# 20_character_HP_DL1414_display_with_SN74.net
KiCad netlist of a schematic drawn in EasyEDA
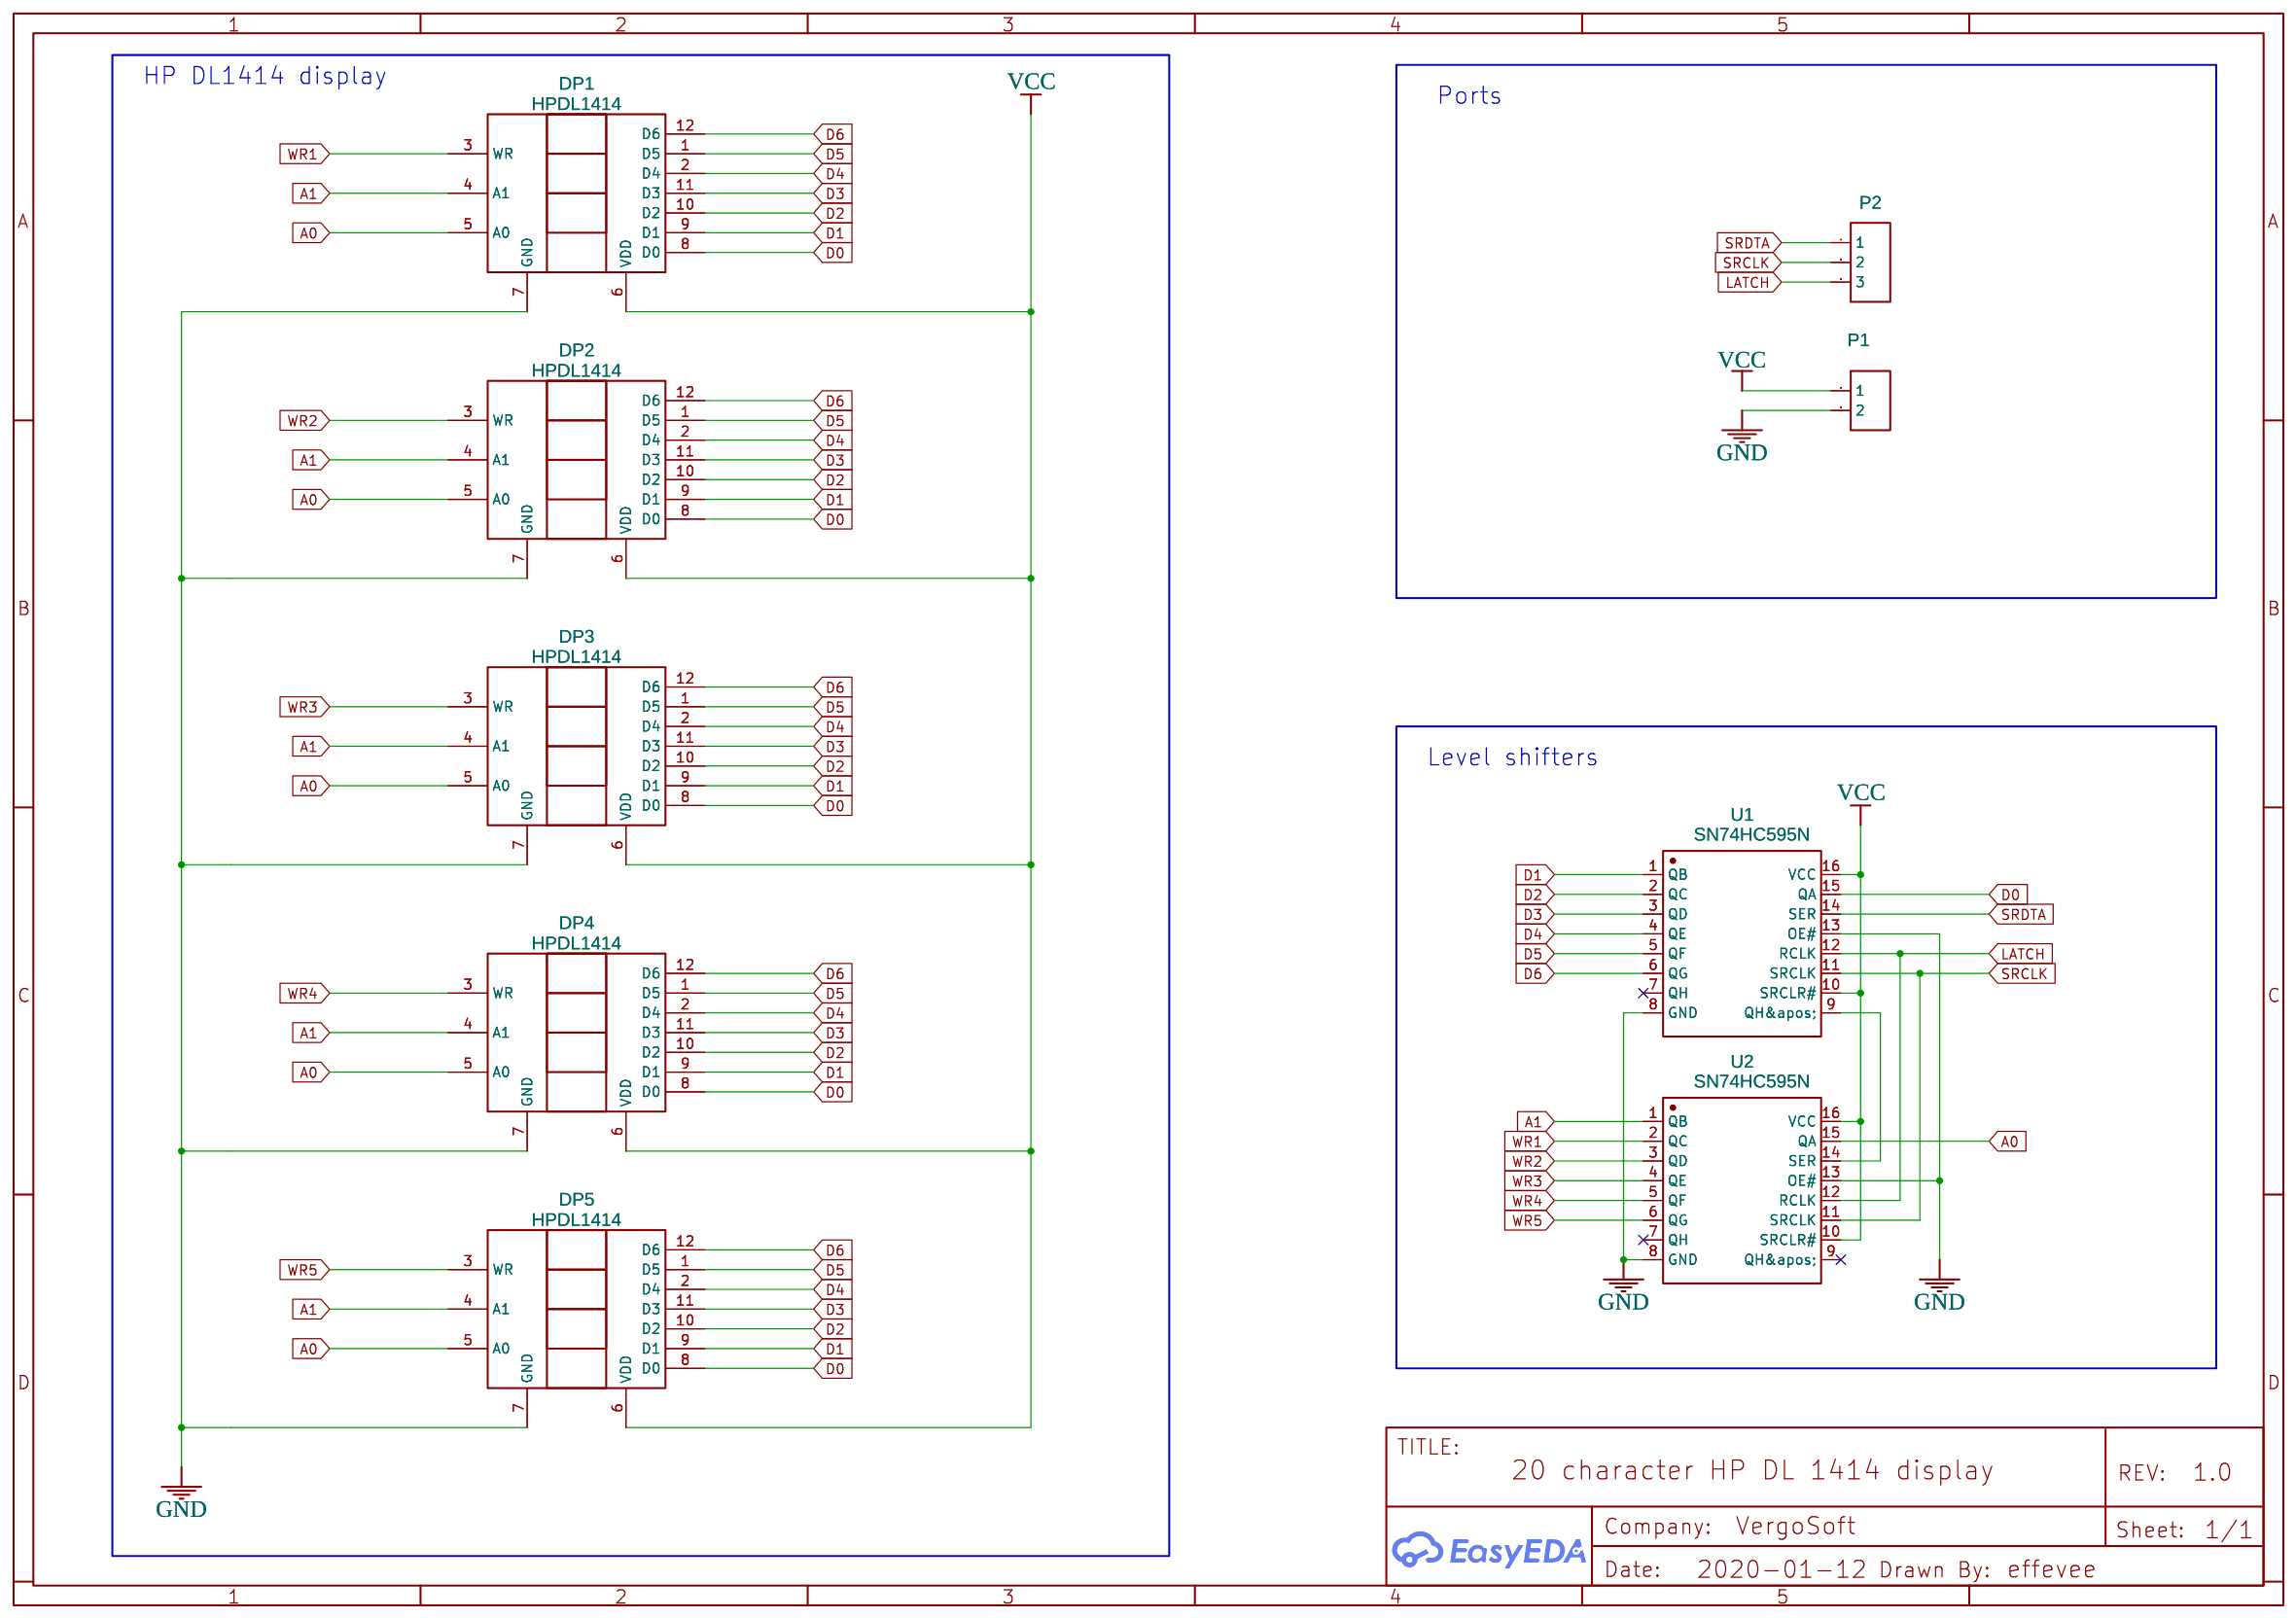
[diagram p0: schematic sheet]

(export (version "E")
  (design (tool "Eeschema 10.0.6"))
  (components
    (comp (ref "DP1")
      (value "HPDL1414")
      (fields (field (name "BOM_Supplier Part") "HPDL-1414"))
      (libsource (lib "") (part "HPDL1414 EFFEVEE"))
    )
    (comp (ref "DP2")
      (value "HPDL1414")
      (fields (field (name "BOM_Supplier Part") "HPDL-1414"))
      (libsource (lib "") (part "HPDL1414 EFFEVEE"))
    )
    (comp (ref "DP3")
      (value "HPDL1414")
      (fields (field (name "BOM_Supplier Part") "HPDL-1414"))
      (libsource (lib "") (part "HPDL1414 EFFEVEE"))
    )
    (comp (ref "DP4")
      (value "HPDL1414")
      (fields (field (name "BOM_Supplier Part") "HPDL-1414"))
      (libsource (lib "") (part "HPDL1414 EFFEVEE"))
    )
    (comp (ref "DP5")
      (value "HPDL1414")
      (fields (field (name "BOM_Supplier Part") "HPDL-1414"))
      (libsource (lib "") (part "HPDL1414 EFFEVEE"))
    )
    (comp (ref "P1")
      (value "Header-Female-2.54_1x2")
      (fields
        (field (name "BOM_Manufacturer Part") "2.54-1*2PFemale")
        (field (name "BOM_Supplier Part") "C49661")
      )
      (libsource (lib "") (part "Header-Female-2.54_1x2"))
    )
    (comp (ref "P2")
      (value "Header-Female-2.54_1x3")
      (fields (field (name "BOM_Supplier Part") "C146243"))
      (libsource (lib "") (part "Header-Female-2.54_1x3"))
    )
    (comp (ref "U1")
      (value "SN74HC595N")
      (fields (field (name "BOM_Supplier Part") "C78711"))
      (libsource (lib "") (part "SN74HC595N"))
    )
    (comp (ref "U2")
      (value "SN74HC595N")
      (fields (field (name "BOM_Supplier Part") "C78711"))
      (libsource (lib "") (part "SN74HC595N"))
    )
  )
  (nets
    (net (code "1") (name "A0") (class "Default")
      (node (ref "DP1") (pin "5") (pinfunction "A0_5") (pintype "unspecified"))
      (node (ref "DP2") (pin "5") (pinfunction "A0_5") (pintype "unspecified"))
      (node (ref "DP3") (pin "5") (pinfunction "A0_5") (pintype "unspecified"))
      (node (ref "DP4") (pin "5") (pinfunction "A0_5") (pintype "unspecified"))
      (node (ref "DP5") (pin "5") (pinfunction "A0_5") (pintype "unspecified"))
      (node (ref "U2") (pin "15") (pinfunction "QA_15") (pintype "unspecified"))
    )
    (net (code "2") (name "A1") (class "Default")
      (node (ref "DP1") (pin "4") (pinfunction "A1_4") (pintype "unspecified"))
      (node (ref "DP2") (pin "4") (pinfunction "A1_4") (pintype "unspecified"))
      (node (ref "DP3") (pin "4") (pinfunction "A1_4") (pintype "unspecified"))
      (node (ref "DP4") (pin "4") (pinfunction "A1_4") (pintype "unspecified"))
      (node (ref "DP5") (pin "4") (pinfunction "A1_4") (pintype "unspecified"))
      (node (ref "U2") (pin "1") (pinfunction "QB_1") (pintype "unspecified"))
    )
    (net (code "3") (name "D0") (class "Default")
      (node (ref "DP1") (pin "8") (pinfunction "D0_8") (pintype "unspecified"))
      (node (ref "DP2") (pin "8") (pinfunction "D0_8") (pintype "unspecified"))
      (node (ref "DP3") (pin "8") (pinfunction "D0_8") (pintype "unspecified"))
      (node (ref "DP4") (pin "8") (pinfunction "D0_8") (pintype "unspecified"))
      (node (ref "DP5") (pin "8") (pinfunction "D0_8") (pintype "unspecified"))
      (node (ref "U1") (pin "15") (pinfunction "QA_15") (pintype "unspecified"))
    )
    (net (code "4") (name "D1") (class "Default")
      (node (ref "DP1") (pin "9") (pinfunction "D1_9") (pintype "unspecified"))
      (node (ref "DP2") (pin "9") (pinfunction "D1_9") (pintype "unspecified"))
      (node (ref "DP3") (pin "9") (pinfunction "D1_9") (pintype "unspecified"))
      (node (ref "DP4") (pin "9") (pinfunction "D1_9") (pintype "unspecified"))
      (node (ref "DP5") (pin "9") (pinfunction "D1_9") (pintype "unspecified"))
      (node (ref "U1") (pin "1") (pinfunction "QB_1") (pintype "unspecified"))
    )
    (net (code "5") (name "D2") (class "Default")
      (node (ref "DP1") (pin "10") (pinfunction "D2_10") (pintype "unspecified"))
      (node (ref "DP2") (pin "10") (pinfunction "D2_10") (pintype "unspecified"))
      (node (ref "DP3") (pin "10") (pinfunction "D2_10") (pintype "unspecified"))
      (node (ref "DP4") (pin "10") (pinfunction "D2_10") (pintype "unspecified"))
      (node (ref "DP5") (pin "10") (pinfunction "D2_10") (pintype "unspecified"))
      (node (ref "U1") (pin "2") (pinfunction "QC_2") (pintype "unspecified"))
    )
    (net (code "6") (name "D3") (class "Default")
      (node (ref "DP1") (pin "11") (pinfunction "D3_11") (pintype "unspecified"))
      (node (ref "DP2") (pin "11") (pinfunction "D3_11") (pintype "unspecified"))
      (node (ref "DP3") (pin "11") (pinfunction "D3_11") (pintype "unspecified"))
      (node (ref "DP4") (pin "11") (pinfunction "D3_11") (pintype "unspecified"))
      (node (ref "DP5") (pin "11") (pinfunction "D3_11") (pintype "unspecified"))
      (node (ref "U1") (pin "3") (pinfunction "QD_3") (pintype "unspecified"))
    )
    (net (code "7") (name "D4") (class "Default")
      (node (ref "DP1") (pin "2") (pinfunction "D4_2") (pintype "unspecified"))
      (node (ref "DP2") (pin "2") (pinfunction "D4_2") (pintype "unspecified"))
      (node (ref "DP3") (pin "2") (pinfunction "D4_2") (pintype "unspecified"))
      (node (ref "DP4") (pin "2") (pinfunction "D4_2") (pintype "unspecified"))
      (node (ref "DP5") (pin "2") (pinfunction "D4_2") (pintype "unspecified"))
      (node (ref "U1") (pin "4") (pinfunction "QE_4") (pintype "unspecified"))
    )
    (net (code "8") (name "D5") (class "Default")
      (node (ref "DP1") (pin "1") (pinfunction "D5_1") (pintype "unspecified"))
      (node (ref "DP2") (pin "1") (pinfunction "D5_1") (pintype "unspecified"))
      (node (ref "DP3") (pin "1") (pinfunction "D5_1") (pintype "unspecified"))
      (node (ref "DP4") (pin "1") (pinfunction "D5_1") (pintype "unspecified"))
      (node (ref "DP5") (pin "1") (pinfunction "D5_1") (pintype "unspecified"))
      (node (ref "U1") (pin "5") (pinfunction "QF_5") (pintype "unspecified"))
    )
    (net (code "9") (name "D6") (class "Default")
      (node (ref "DP1") (pin "12") (pinfunction "D6_12") (pintype "unspecified"))
      (node (ref "DP2") (pin "12") (pinfunction "D6_12") (pintype "unspecified"))
      (node (ref "DP3") (pin "12") (pinfunction "D6_12") (pintype "unspecified"))
      (node (ref "DP4") (pin "12") (pinfunction "D6_12") (pintype "unspecified"))
      (node (ref "DP5") (pin "12") (pinfunction "D6_12") (pintype "unspecified"))
      (node (ref "U1") (pin "6") (pinfunction "QG_6") (pintype "unspecified"))
    )
    (net (code "10") (name "GND") (class "Default")
      (node (ref "DP1") (pin "7") (pinfunction "GND_7") (pintype "unspecified"))
      (node (ref "DP2") (pin "7") (pinfunction "GND_7") (pintype "unspecified"))
      (node (ref "DP3") (pin "7") (pinfunction "GND_7") (pintype "unspecified"))
      (node (ref "DP4") (pin "7") (pinfunction "GND_7") (pintype "unspecified"))
      (node (ref "DP5") (pin "7") (pinfunction "GND_7") (pintype "unspecified"))
      (node (ref "P1") (pin "2") (pinfunction "2_2") (pintype "input"))
      (node (ref "U1") (pin "13") (pinfunction "OE#_13") (pintype "unspecified"))
      (node (ref "U1") (pin "8") (pinfunction "GND_8") (pintype "unspecified"))
      (node (ref "U2") (pin "13") (pinfunction "OE#_13") (pintype "unspecified"))
      (node (ref "U2") (pin "8") (pinfunction "GND_8") (pintype "unspecified"))
    )
    (net (code "11") (name "LATCH") (class "Default")
      (node (ref "P2") (pin "3") (pinfunction "3_3") (pintype "input"))
      (node (ref "U1") (pin "12") (pinfunction "RCLK_12") (pintype "unspecified"))
      (node (ref "U2") (pin "12") (pinfunction "RCLK_12") (pintype "unspecified"))
    )
    (net (code "12") (name "Net-(U1-QH&apos;)") (class "Default")
      (node (ref "U1") (pin "9") (pinfunction "QH&apos;_9") (pintype "unspecified"))
      (node (ref "U2") (pin "14") (pinfunction "SER_14") (pintype "unspecified"))
    )
    (net (code "13") (name "SRCLK") (class "Default")
      (node (ref "P2") (pin "2") (pinfunction "2_2") (pintype "input"))
      (node (ref "U1") (pin "11") (pinfunction "SRCLK_11") (pintype "unspecified"))
      (node (ref "U2") (pin "11") (pinfunction "SRCLK_11") (pintype "unspecified"))
    )
    (net (code "14") (name "SRDTA") (class "Default")
      (node (ref "P2") (pin "1") (pinfunction "1_1") (pintype "input"))
      (node (ref "U1") (pin "14") (pinfunction "SER_14") (pintype "unspecified"))
    )
    (net (code "15") (name "VCC") (class "Default")
      (node (ref "DP1") (pin "6") (pinfunction "VDD_6") (pintype "unspecified"))
      (node (ref "DP2") (pin "6") (pinfunction "VDD_6") (pintype "unspecified"))
      (node (ref "DP3") (pin "6") (pinfunction "VDD_6") (pintype "unspecified"))
      (node (ref "DP4") (pin "6") (pinfunction "VDD_6") (pintype "unspecified"))
      (node (ref "DP5") (pin "6") (pinfunction "VDD_6") (pintype "unspecified"))
      (node (ref "P1") (pin "1") (pinfunction "1_1") (pintype "input"))
      (node (ref "U1") (pin "10") (pinfunction "SRCLR#_10") (pintype "unspecified"))
      (node (ref "U1") (pin "16") (pinfunction "VCC_16") (pintype "unspecified"))
      (node (ref "U2") (pin "10") (pinfunction "SRCLR#_10") (pintype "unspecified"))
      (node (ref "U2") (pin "16") (pinfunction "VCC_16") (pintype "unspecified"))
    )
    (net (code "16") (name "WR1") (class "Default")
      (node (ref "DP1") (pin "3") (pinfunction "WR_3") (pintype "unspecified"))
      (node (ref "U2") (pin "2") (pinfunction "QC_2") (pintype "unspecified"))
    )
    (net (code "17") (name "WR2") (class "Default")
      (node (ref "DP2") (pin "3") (pinfunction "WR_3") (pintype "unspecified"))
      (node (ref "U2") (pin "3") (pinfunction "QD_3") (pintype "unspecified"))
    )
    (net (code "18") (name "WR3") (class "Default")
      (node (ref "DP3") (pin "3") (pinfunction "WR_3") (pintype "unspecified"))
      (node (ref "U2") (pin "4") (pinfunction "QE_4") (pintype "unspecified"))
    )
    (net (code "19") (name "WR4") (class "Default")
      (node (ref "DP4") (pin "3") (pinfunction "WR_3") (pintype "unspecified"))
      (node (ref "U2") (pin "5") (pinfunction "QF_5") (pintype "unspecified"))
    )
    (net (code "20") (name "WR5") (class "Default")
      (node (ref "DP5") (pin "3") (pinfunction "WR_3") (pintype "unspecified"))
      (node (ref "U2") (pin "6") (pinfunction "QG_6") (pintype "unspecified"))
    )
    (net (code "21") (name "unconnected-(U1-QH-Pad7)") (class "Default")
      (node (ref "U1") (pin "7") (pinfunction "QH_7") (pintype "unspecified+no_connect"))
    )
    (net (code "22") (name "unconnected-(U2-QH&apos;-Pad9)") (class "Default")
      (node (ref "U2") (pin "9") (pinfunction "QH&apos;_9") (pintype "unspecified+no_connect"))
    )
    (net (code "23") (name "unconnected-(U2-QH-Pad7)") (class "Default")
      (node (ref "U2") (pin "7") (pinfunction "QH_7") (pintype "unspecified+no_connect"))
    )
  )
)
